# Schematic_Sensing_Module.net
KiCad netlist of a schematic drawn in EAGLE
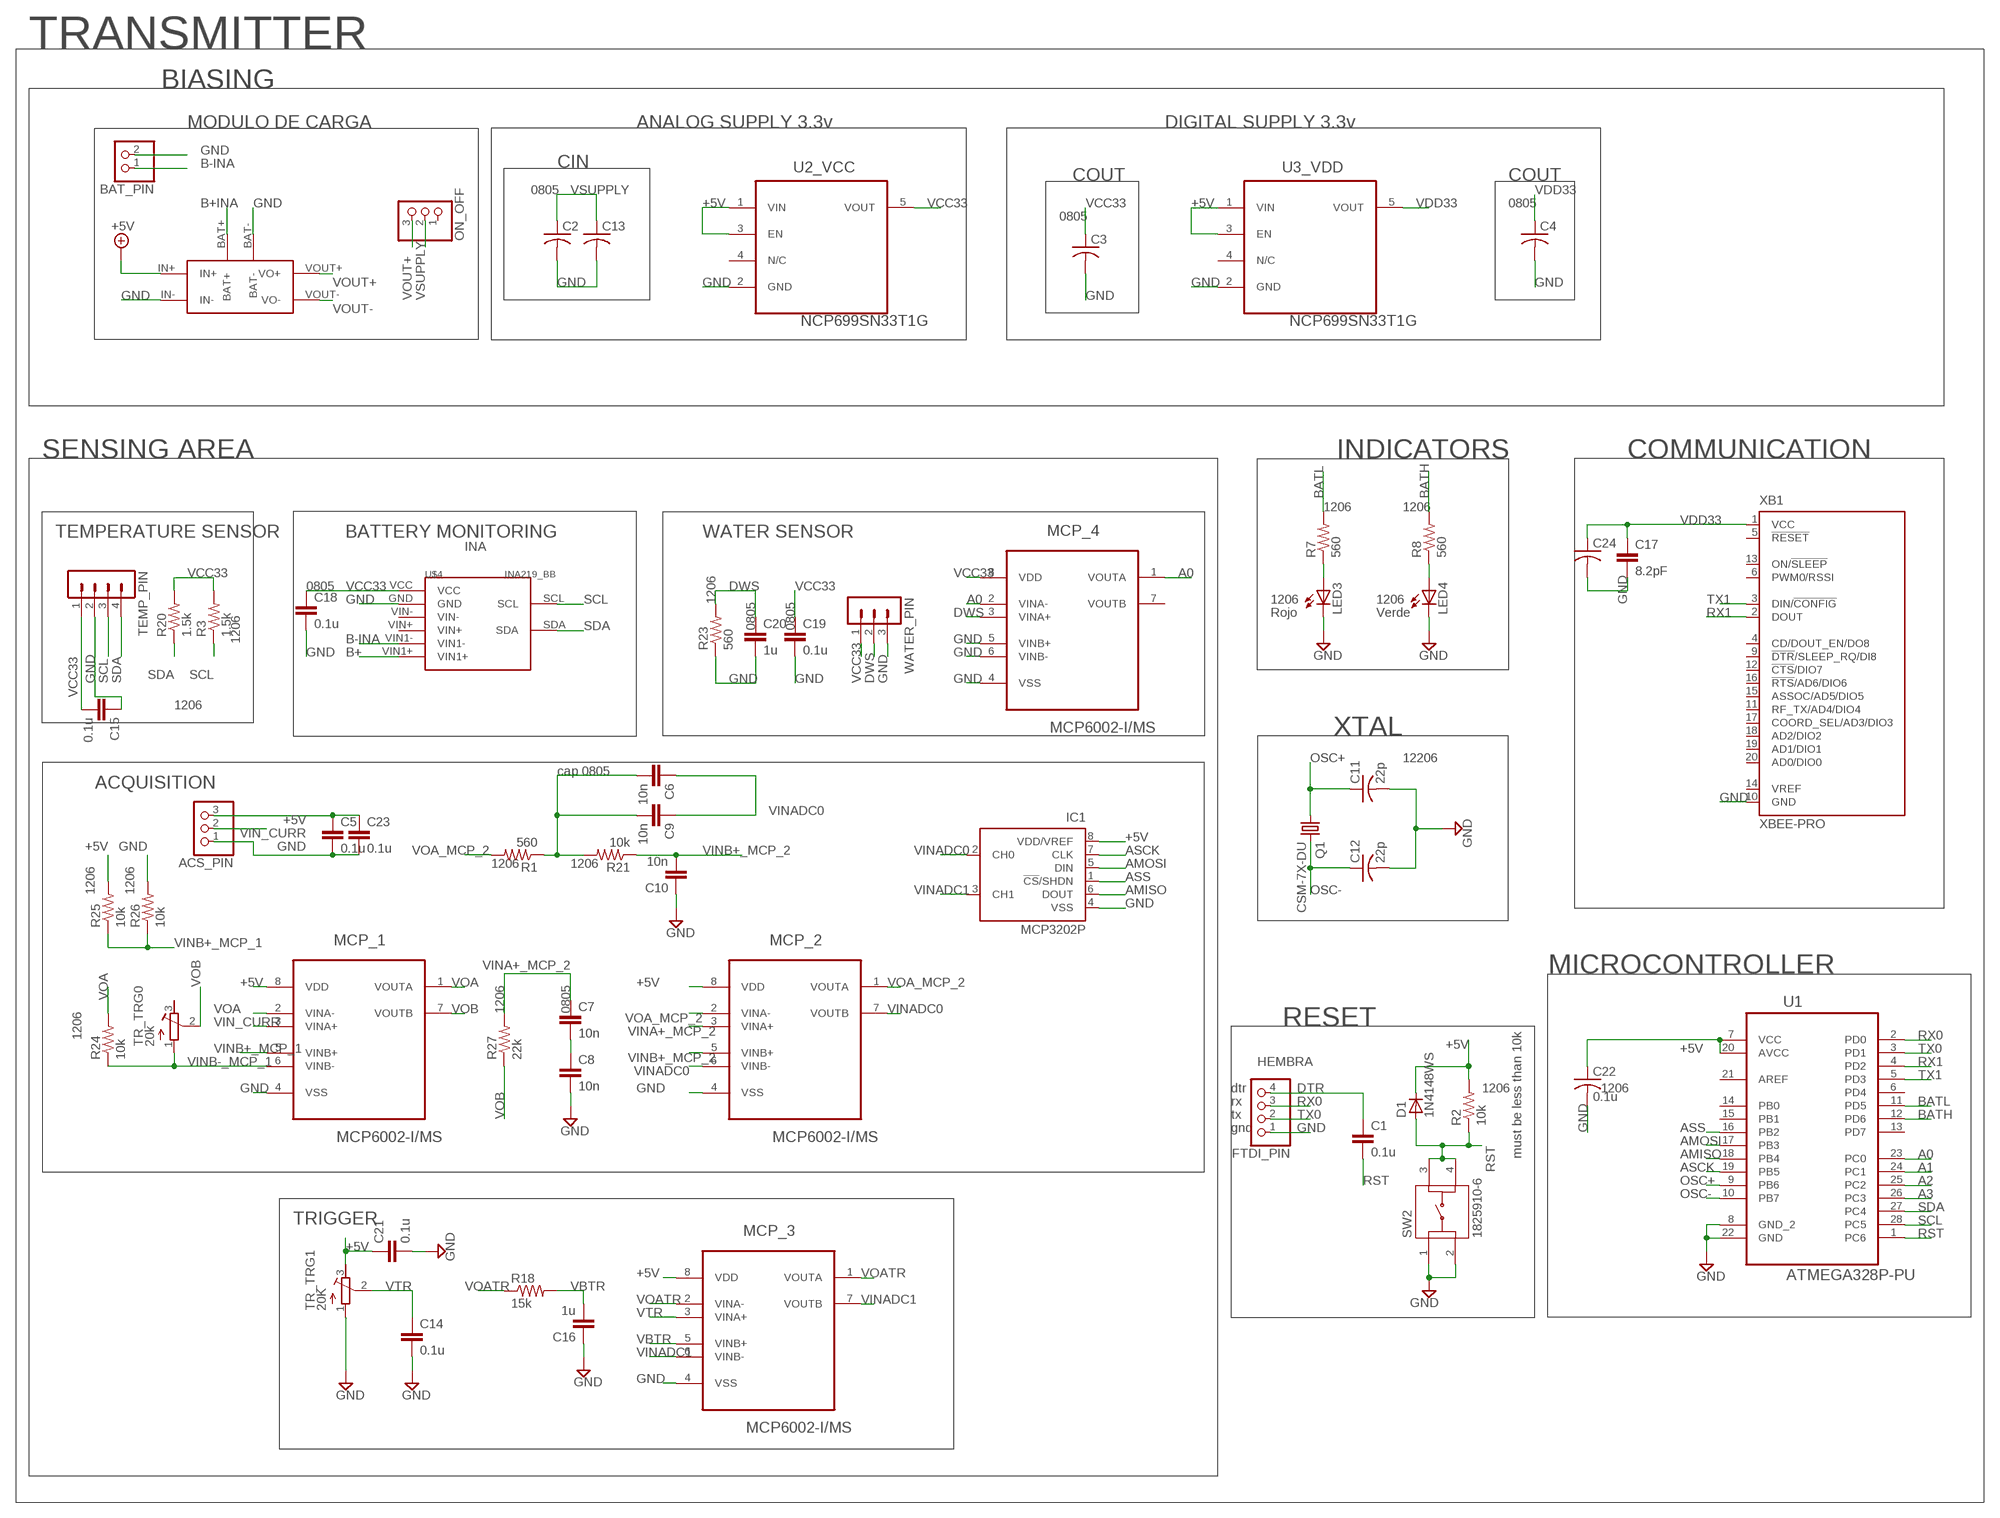
[diagram p0: schematic, sheet 1]

(export (version "E")
  (design (tool "Eeschema 10.0.6"))
  (components
    (comp (ref "ACS_PIN")
      (value "PINHD-1X3")
      (footprint "eagle-import:1X03")
      (libsource (lib "eagle-import") (part "PINHD-1X3"))
    )
    (comp (ref "BAT_PIN")
      (value "PINHD-1X2")
      (footprint "eagle-import:1X02")
      (libsource (lib "eagle-import") (part "PINHD-1X2"))
    )
    (comp (ref "C1")
      (value "0.1u")
      (footprint "eagle-import:C0805")
      (libsource (lib "eagle-import") (part "C-EUC0805"))
    )
    (comp (ref "C2")
      (value "C-USC0805")
      (footprint "eagle-import:C0805")
      (libsource (lib "eagle-import") (part "C-USC0805"))
    )
    (comp (ref "C3")
      (value "C-USC0805")
      (footprint "eagle-import:C0805")
      (libsource (lib "eagle-import") (part "C-USC0805"))
    )
    (comp (ref "C4")
      (value "C-USC0805")
      (footprint "eagle-import:C0805")
      (libsource (lib "eagle-import") (part "C-USC0805"))
    )
    (comp (ref "C5")
      (value "0.1u")
      (footprint "eagle-import:C0805")
      (libsource (lib "eagle-import") (part "C-EUC0805"))
    )
    (comp (ref "C6")
      (value "10n")
      (footprint "eagle-import:C0805")
      (libsource (lib "eagle-import") (part "C-EUC0805"))
    )
    (comp (ref "C7")
      (value "10n")
      (footprint "eagle-import:C0805")
      (libsource (lib "eagle-import") (part "C-EUC0805"))
    )
    (comp (ref "C8")
      (value "10n")
      (footprint "eagle-import:C0805")
      (libsource (lib "eagle-import") (part "C-EUC0805"))
    )
    (comp (ref "C9")
      (value "10n")
      (footprint "eagle-import:C0805")
      (libsource (lib "eagle-import") (part "C-EUC0805"))
    )
    (comp (ref "C10")
      (value "10n")
      (footprint "eagle-import:C0805")
      (libsource (lib "eagle-import") (part "C-EUC0805"))
    )
    (comp (ref "C11")
      (value "22p")
      (footprint "eagle-import:C1206")
      (libsource (lib "eagle-import") (part "C-USC1206"))
    )
    (comp (ref "C12")
      (value "22p")
      (footprint "eagle-import:C1206")
      (libsource (lib "eagle-import") (part "C-USC1206"))
    )
    (comp (ref "C13")
      (value "C-USC0805")
      (footprint "eagle-import:C0805")
      (libsource (lib "eagle-import") (part "C-USC0805"))
    )
    (comp (ref "C14")
      (value "0.1u")
      (footprint "eagle-import:C0805")
      (libsource (lib "eagle-import") (part "C-EUC0805"))
    )
    (comp (ref "C15")
      (value "0.1u")
      (footprint "eagle-import:C0805")
      (libsource (lib "eagle-import") (part "C-EUC0805"))
    )
    (comp (ref "C16")
      (value "1u")
      (footprint "eagle-import:C0805")
      (libsource (lib "eagle-import") (part "C-EUC0805"))
    )
    (comp (ref "C17")
      (value "8.2pF")
      (footprint "eagle-import:C0805")
      (libsource (lib "eagle-import") (part "C-EUC0805"))
    )
    (comp (ref "C18")
      (value "0.1u")
      (footprint "eagle-import:C0805")
      (libsource (lib "eagle-import") (part "C-EUC0805"))
    )
    (comp (ref "C19")
      (value "0.1u")
      (footprint "eagle-import:C0805")
      (libsource (lib "eagle-import") (part "C-EUC0805"))
    )
    (comp (ref "C20")
      (value "1u")
      (footprint "eagle-import:C0805")
      (libsource (lib "eagle-import") (part "C-EUC0805"))
    )
    (comp (ref "C21")
      (value "0.1u")
      (footprint "eagle-import:C0805")
      (libsource (lib "eagle-import") (part "C-EUC0805"))
    )
    (comp (ref "C22")
      (value "0.1u")
      (footprint "eagle-import:C1206")
      (libsource (lib "eagle-import") (part "C-USC1206"))
    )
    (comp (ref "C23")
      (value "0.1u")
      (footprint "eagle-import:C0805")
      (libsource (lib "eagle-import") (part "C-EUC0805"))
    )
    (comp (ref "C24")
      (value "C-USC0805")
      (footprint "eagle-import:C0805")
      (libsource (lib "eagle-import") (part "C-USC0805"))
    )
    (comp (ref "D1")
      (value "1N4148WS")
      (footprint "eagle-import:SOD323")
      (fields (field (name "MF") "ON Semiconductor"))
      (libsource (lib "eagle-import") (part "1N4148WS"))
    )
    (comp (ref "FTDI_PIN")
      (value "PINHD-1X4")
      (footprint "eagle-import:1X04")
      (libsource (lib "eagle-import") (part "PINHD-1X4"))
    )
    (comp (ref "IC1")
      (value "MCP3202P")
      (footprint "eagle-import:DIL8")
      (fields (field (name "MF") "MICROCHIP") (field (name "MPN") "MCP3202-CI/P"))
      (libsource (lib "eagle-import") (part "MCP3202P"))
    )
    (comp (ref "LED3")
      (value "LEDCHIPLED_1206")
      (footprint "eagle-import:CHIPLED_1206")
      (libsource (lib "eagle-import") (part "LEDCHIPLED_1206"))
    )
    (comp (ref "LED4")
      (value "LEDCHIPLED_1206")
      (footprint "eagle-import:CHIPLED_1206")
      (libsource (lib "eagle-import") (part "LEDCHIPLED_1206"))
    )
    (comp (ref "MCP_1")
      (value "MCP6002-I/MS")
      (footprint "eagle-import:SOP65P490X110-8N")
      (fields (field (name "MF") "Microchip"))
      (libsource (lib "eagle-import") (part "MCP6002-I_MS-2_MCP6002-I/MS"))
    )
    (comp (ref "MCP_2")
      (value "MCP6002-I/MS")
      (footprint "eagle-import:SOP65P490X110-8N")
      (fields (field (name "DIGI-KEY_PART_NUMBER") "MCP6002-I/MS-ND") (field (name "MF") "Microchip"))
      (libsource (lib "eagle-import") (part "MCP6002-I/MS"))
    )
    (comp (ref "MCP_3")
      (value "MCP6002-I/MS")
      (footprint "eagle-import:SOP65P490X110-8N")
      (fields (field (name "DIGI-KEY_PART_NUMBER") "MCP6002-I/MS-ND") (field (name "MF") "Microchip"))
      (libsource (lib "eagle-import") (part "MCP6002-I/MS"))
    )
    (comp (ref "MCP_4")
      (value "MCP6002-I/MS")
      (footprint "eagle-import:SOP65P490X110-8N")
      (fields (field (name "DIGI-KEY_PART_NUMBER") "MCP6002-I/MS-ND") (field (name "MF") "Microchip"))
      (libsource (lib "eagle-import") (part "MCP6002-I/MS"))
    )
    (comp (ref "ON_OFF")
      (value "PINHD-1X3")
      (footprint "eagle-import:1X03")
      (libsource (lib "eagle-import") (part "PINHD-1X3"))
    )
    (comp (ref "Q1")
      (value "CSM-7X-DU")
      (footprint "eagle-import:CSM-7X-DU")
      (libsource (lib "eagle-import") (part "CSM-7X-DU"))
    )
    (comp (ref "R1")
      (value "560")
      (footprint "eagle-import:R1206")
      (libsource (lib "eagle-import") (part "R-US_R1206"))
    )
    (comp (ref "R2")
      (value "10k")
      (footprint "eagle-import:R1206")
      (libsource (lib "eagle-import") (part "R-US_R1206"))
    )
    (comp (ref "R3")
      (value "1.5k")
      (footprint "eagle-import:R1206")
      (libsource (lib "eagle-import") (part "R-US_R1206"))
    )
    (comp (ref "R7")
      (value "560")
      (footprint "eagle-import:R1206")
      (libsource (lib "eagle-import") (part "R-US_R1206"))
    )
    (comp (ref "R8")
      (value "560")
      (footprint "eagle-import:R1206")
      (libsource (lib "eagle-import") (part "R-US_R1206"))
    )
    (comp (ref "R18")
      (value "15k")
      (footprint "eagle-import:R0805")
      (libsource (lib "eagle-import") (part "resistor_R-US_R0805"))
    )
    (comp (ref "R20")
      (value "1.5k")
      (footprint "eagle-import:R1206")
      (libsource (lib "eagle-import") (part "R-US_R1206"))
    )
    (comp (ref "R21")
      (value "10k")
      (footprint "eagle-import:R1206")
      (libsource (lib "eagle-import") (part "R-US_R1206"))
    )
    (comp (ref "R23")
      (value "560")
      (footprint "eagle-import:R1206")
      (libsource (lib "eagle-import") (part "R-US_R1206"))
    )
    (comp (ref "R24")
      (value "10k")
      (footprint "eagle-import:R1206")
      (libsource (lib "eagle-import") (part "R-US_R1206"))
    )
    (comp (ref "R25")
      (value "10k")
      (footprint "eagle-import:R1206")
      (libsource (lib "eagle-import") (part "R-US_R1206"))
    )
    (comp (ref "R26")
      (value "10k")
      (footprint "eagle-import:R1206")
      (libsource (lib "eagle-import") (part "R-US_R1206"))
    )
    (comp (ref "R27")
      (value "22k")
      (footprint "eagle-import:R1206")
      (libsource (lib "eagle-import") (part "R-US_R1206"))
    )
    (comp (ref "SW2")
      (value "1825910-6")
      (footprint "eagle-import:SW_1825910-6-4")
      (fields (field (name "MF") "TE Connectivity"))
      (libsource (lib "eagle-import") (part "1825910-6"))
    )
    (comp (ref "TEMP_PIN")
      (value "MA04-1")
      (footprint "eagle-import:MA04-1")
      (libsource (lib "eagle-import") (part "MA04-1"))
    )
    (comp (ref "TR_TRG0")
      (value "20k")
      (footprint "eagle-import:RTRIM64W")
      (libsource (lib "eagle-import") (part "R-TRIMM64W"))
    )
    (comp (ref "TR_TRG1")
      (value "20K")
      (footprint "eagle-import:RTRIM64W")
      (libsource (lib "eagle-import") (part "R-TRIMM64W"))
    )
    (comp (ref "U$1")
      (value "MODULO_CARGA_DEVICE")
      (footprint "eagle-import:MODULO_CARGA")
      (libsource (lib "eagle-import") (part "MODULO_CARGA_DEVICE"))
    )
    (comp (ref "U$4")
      (value "INA219_BB")
      (footprint "eagle-import:INA219_BB")
      (libsource (lib "eagle-import") (part "INA219_BB"))
    )
    (comp (ref "U1")
      (value "ATMEGA328P-PU")
      (footprint "eagle-import:DIP254P762X457-28")
      (libsource (lib "eagle-import") (part "ATMEGA328P-PU"))
    )
    (comp (ref "U2_VCC")
      (value "NCP699SN33T1G")
      (footprint "eagle-import:SOT95P275X110-5N")
      (fields
        (field (name "DIGI-KEY_PART_NUMBER") "NCP699SN33T1GOSCT-ND")
        (field (name "MF") "ON Semiconductor")
      )
      (libsource (lib "eagle-import") (part "NCP699SN33T1G"))
    )
    (comp (ref "U3_VDD")
      (value "NCP699SN33T1G")
      (footprint "eagle-import:SOT95P275X110-5N")
      (fields
        (field (name "DIGI-KEY_PART_NUMBER") "NCP699SN33T1GOSCT-ND")
        (field (name "MF") "ON Semiconductor")
      )
      (libsource (lib "eagle-import") (part "NCP699SN33T1G"))
    )
    (comp (ref "WATER_PIN")
      (value "MA03-1")
      (footprint "eagle-import:MA03-1")
      (libsource (lib "eagle-import") (part "MA03-1"))
    )
    (comp (ref "XB1")
      (value "XBEE-PRO")
      (footprint "eagle-import:XBEE-PRO")
      (fields (field (name "MPN") "XBP24-AWI-001"))
      (libsource (lib "eagle-import") (part "XBEE-PRO"))
    )
  )
  (nets
    (net (code "1") (name "+5V") (class "Default")
      (node (ref "ACS_PIN") (pin "3") (pinfunction "3_3") (pintype "passive"))
      (node (ref "C21") (pin "1") (pinfunction "1_1") (pintype "passive"))
      (node (ref "C22") (pin "1") (pinfunction "1_1") (pintype "passive"))
      (node (ref "C23") (pin "1") (pinfunction "1_1") (pintype "passive"))
      (node (ref "C5") (pin "1") (pinfunction "1_1") (pintype "passive"))
      (node (ref "D1") (pin "C") (pinfunction "C_C") (pintype "passive"))
      (node (ref "IC1") (pin "8") (pinfunction "VDD/VREF_8") (pintype "input"))
      (node (ref "MCP_1") (pin "8") (pinfunction "VDD_8") (pintype "power_in"))
      (node (ref "MCP_2") (pin "8") (pinfunction "VDD_8") (pintype "power_in"))
      (node (ref "MCP_3") (pin "8") (pinfunction "VDD_8") (pintype "power_in"))
      (node (ref "R2") (pin "2") (pinfunction "2_2") (pintype "passive"))
      (node (ref "R25") (pin "2") (pinfunction "2_2") (pintype "passive"))
      (node (ref "TR_TRG1") (pin "3") (pinfunction "E_3") (pintype "passive"))
      (node (ref "U$1") (pin "IN+") (pinfunction "IN+_IN+") (pintype "bidirectional"))
      (node (ref "U1") (pin "20") (pinfunction "AVCC_20") (pintype "power_in"))
      (node (ref "U1") (pin "7") (pinfunction "VCC_7") (pintype "power_in"))
      (node (ref "U2_VCC") (pin "1") (pinfunction "VIN_1") (pintype "power_in"))
      (node (ref "U2_VCC") (pin "3") (pinfunction "EN_3") (pintype "input"))
      (node (ref "U3_VDD") (pin "1") (pinfunction "VIN_1") (pintype "power_in"))
      (node (ref "U3_VDD") (pin "3") (pinfunction "EN_3") (pintype "input"))
    )
    (net (code "2") (name "/A0") (class "Default")
      (node (ref "MCP_4") (pin "1") (pinfunction "VOUTA_1") (pintype "output"))
      (node (ref "MCP_4") (pin "2") (pinfunction "VINA-_2") (pintype "input"))
      (node (ref "U1") (pin "23") (pinfunction "PC0_23") (pintype "bidirectional"))
    )
    (net (code "3") (name "/A1") (class "Default")
      (node (ref "U1") (pin "24") (pinfunction "PC1_24") (pintype "bidirectional"))
    )
    (net (code "4") (name "/A2") (class "Default")
      (node (ref "U1") (pin "25") (pinfunction "PC2_25") (pintype "bidirectional"))
    )
    (net (code "5") (name "/A3") (class "Default")
      (node (ref "U1") (pin "26") (pinfunction "PC3_26") (pintype "bidirectional"))
    )
    (net (code "6") (name "/AMISO") (class "Default")
      (node (ref "IC1") (pin "6") (pinfunction "DOUT_6") (pintype "input"))
      (node (ref "U1") (pin "18") (pinfunction "PB4_18") (pintype "bidirectional"))
    )
    (net (code "7") (name "/AMOSI") (class "Default")
      (node (ref "IC1") (pin "5") (pinfunction "DIN_5") (pintype "input"))
      (node (ref "U1") (pin "17") (pinfunction "PB3_17") (pintype "bidirectional"))
    )
    (net (code "8") (name "/ASCK") (class "Default")
      (node (ref "IC1") (pin "7") (pinfunction "CLK_7") (pintype "input"))
      (node (ref "U1") (pin "19") (pinfunction "PB5_19") (pintype "bidirectional"))
    )
    (net (code "9") (name "/ASS") (class "Default")
      (node (ref "IC1") (pin "1") (pinfunction "~{CS}/SHDN_1") (pintype "input"))
      (node (ref "U1") (pin "16") (pinfunction "PB2_16") (pintype "bidirectional"))
    )
    (net (code "10") (name "/B+") (class "Default")
      (node (ref "U$4") (pin "VIN1+") (pinfunction "VIN1+_VIN1+") (pintype "bidirectional"))
    )
    (net (code "11") (name "/B+INA") (class "Default")
      (node (ref "U$1") (pin "BAT+") (pinfunction "BAT+_BAT+") (pintype "bidirectional"))
    )
    (net (code "12") (name "/B-INA") (class "Default")
      (node (ref "BAT_PIN") (pin "1") (pinfunction "1_1") (pintype "passive"))
      (node (ref "U$4") (pin "VIN1-") (pinfunction "VIN1-_VIN1-") (pintype "bidirectional"))
    )
    (net (code "13") (name "/BATH") (class "Default")
      (node (ref "R8") (pin "2") (pinfunction "2_2") (pintype "passive"))
      (node (ref "U1") (pin "12") (pinfunction "PD6_12") (pintype "bidirectional"))
    )
    (net (code "14") (name "/BATL") (class "Default")
      (node (ref "R7") (pin "2") (pinfunction "2_2") (pintype "passive"))
      (node (ref "U1") (pin "11") (pinfunction "PD5_11") (pintype "bidirectional"))
    )
    (net (code "15") (name "/DTR") (class "Default")
      (node (ref "C1") (pin "1") (pinfunction "1_1") (pintype "passive"))
      (node (ref "FTDI_PIN") (pin "4") (pinfunction "4_4") (pintype "passive"))
    )
    (net (code "16") (name "/DWS") (class "Default")
      (node (ref "C20") (pin "1") (pinfunction "1_1") (pintype "passive"))
      (node (ref "MCP_4") (pin "3") (pinfunction "VINA+_3") (pintype "input"))
      (node (ref "R23") (pin "2") (pinfunction "2_2") (pintype "passive"))
      (node (ref "WATER_PIN") (pin "2") (pinfunction "2_2") (pintype "passive"))
    )
    (net (code "17") (name "/OSC+") (class "Default")
      (node (ref "C11") (pin "1") (pinfunction "1_1") (pintype "passive"))
      (node (ref "Q1") (pin "1") (pinfunction "1_1") (pintype "passive"))
      (node (ref "U1") (pin "9") (pinfunction "PB6_9") (pintype "bidirectional"))
    )
    (net (code "18") (name "/OSC-") (class "Default")
      (node (ref "C12") (pin "1") (pinfunction "1_1") (pintype "passive"))
      (node (ref "Q1") (pin "2") (pinfunction "2_2") (pintype "passive"))
      (node (ref "U1") (pin "10") (pinfunction "PB7_10") (pintype "bidirectional"))
    )
    (net (code "19") (name "/RST") (class "Default")
      (node (ref "C1") (pin "2") (pinfunction "2_2") (pintype "passive"))
      (node (ref "D1") (pin "A") (pinfunction "A_A") (pintype "passive"))
      (node (ref "R2") (pin "1") (pinfunction "1_1") (pintype "passive"))
      (node (ref "SW2") (pin "3") (pinfunction "3_3") (pintype "passive"))
      (node (ref "SW2") (pin "4") (pinfunction "4_4") (pintype "passive"))
      (node (ref "U1") (pin "1") (pinfunction "PC6_1") (pintype "bidirectional"))
    )
    (net (code "20") (name "/RX0") (class "Default")
      (node (ref "FTDI_PIN") (pin "3") (pinfunction "3_3") (pintype "passive"))
      (node (ref "U1") (pin "2") (pinfunction "PD0_2") (pintype "bidirectional"))
    )
    (net (code "21") (name "/RX1") (class "Default")
      (node (ref "U1") (pin "4") (pinfunction "PD2_4") (pintype "bidirectional"))
      (node (ref "XB1") (pin "2") (pinfunction "DOUT_2") (pintype "output"))
    )
    (net (code "22") (name "/SCL") (class "Default")
      (node (ref "R3") (pin "1") (pinfunction "1_1") (pintype "passive"))
      (node (ref "TEMP_PIN") (pin "3") (pinfunction "3_3") (pintype "passive"))
      (node (ref "U$4") (pin "SCL") (pinfunction "SCL_SCL") (pintype "bidirectional"))
      (node (ref "U1") (pin "28") (pinfunction "PC5_28") (pintype "bidirectional"))
    )
    (net (code "23") (name "/SDA") (class "Default")
      (node (ref "R20") (pin "1") (pinfunction "1_1") (pintype "passive"))
      (node (ref "TEMP_PIN") (pin "4") (pinfunction "4_4") (pintype "passive"))
      (node (ref "U$4") (pin "SDA") (pinfunction "SDA_SDA") (pintype "bidirectional"))
      (node (ref "U1") (pin "27") (pinfunction "PC4_27") (pintype "bidirectional"))
    )
    (net (code "24") (name "/TX0") (class "Default")
      (node (ref "FTDI_PIN") (pin "2") (pinfunction "2_2") (pintype "passive"))
      (node (ref "U1") (pin "3") (pinfunction "PD1_3") (pintype "bidirectional"))
    )
    (net (code "25") (name "/TX1") (class "Default")
      (node (ref "U1") (pin "5") (pinfunction "PD3_5") (pintype "bidirectional"))
      (node (ref "XB1") (pin "3") (pinfunction "DIN/~{CONFIG}_3") (pintype "input"))
    )
    (net (code "26") (name "/VBTR") (class "Default")
      (node (ref "C16") (pin "2") (pinfunction "2_2") (pintype "passive"))
      (node (ref "MCP_3") (pin "5") (pinfunction "VINB+_5") (pintype "input"))
      (node (ref "R18") (pin "2") (pinfunction "2_2") (pintype "passive"))
    )
    (net (code "27") (name "/VCC33") (class "Default")
      (node (ref "C15") (pin "2") (pinfunction "2_2") (pintype "passive"))
      (node (ref "C18") (pin "1") (pinfunction "1_1") (pintype "passive"))
      (node (ref "C19") (pin "1") (pinfunction "1_1") (pintype "passive"))
      (node (ref "C3") (pin "1") (pinfunction "1_1") (pintype "passive"))
      (node (ref "MCP_4") (pin "8") (pinfunction "VDD_8") (pintype "power_in"))
      (node (ref "R20") (pin "2") (pinfunction "2_2") (pintype "passive"))
      (node (ref "R3") (pin "2") (pinfunction "2_2") (pintype "passive"))
      (node (ref "TEMP_PIN") (pin "1") (pinfunction "1_1") (pintype "passive"))
      (node (ref "U$4") (pin "VCC") (pinfunction "VCC_VCC") (pintype "bidirectional"))
      (node (ref "U2_VCC") (pin "5") (pinfunction "VOUT_5") (pintype "output"))
      (node (ref "WATER_PIN") (pin "1") (pinfunction "1_1") (pintype "passive"))
    )
    (net (code "28") (name "/VDD33") (class "Default")
      (node (ref "C17") (pin "1") (pinfunction "1_1") (pintype "passive"))
      (node (ref "C24") (pin "1") (pinfunction "1_1") (pintype "passive"))
      (node (ref "C4") (pin "1") (pinfunction "1_1") (pintype "passive"))
      (node (ref "U3_VDD") (pin "5") (pinfunction "VOUT_5") (pintype "output"))
      (node (ref "XB1") (pin "1") (pinfunction "VCC_1") (pintype "power_in"))
    )
    (net (code "29") (name "/VINA+_MCP_2") (class "Default")
      (node (ref "C7") (pin "1") (pinfunction "1_1") (pintype "passive"))
      (node (ref "MCP_2") (pin "3") (pinfunction "VINA+_3") (pintype "input"))
      (node (ref "R27") (pin "2") (pinfunction "2_2") (pintype "passive"))
    )
    (net (code "30") (name "/VINADC0") (class "Default")
      (node (ref "C6") (pin "1") (pinfunction "1_1") (pintype "passive"))
      (node (ref "C9") (pin "1") (pinfunction "1_1") (pintype "passive"))
      (node (ref "IC1") (pin "2") (pinfunction "CH0_2") (pintype "input"))
      (node (ref "MCP_2") (pin "6") (pinfunction "VINB-_6") (pintype "input"))
      (node (ref "MCP_2") (pin "7") (pinfunction "VOUTB_7") (pintype "output"))
    )
    (net (code "31") (name "/VINADC1") (class "Default")
      (node (ref "IC1") (pin "3") (pinfunction "CH1_3") (pintype "input"))
      (node (ref "MCP_3") (pin "6") (pinfunction "VINB-_6") (pintype "input"))
      (node (ref "MCP_3") (pin "7") (pinfunction "VOUTB_7") (pintype "output"))
    )
    (net (code "32") (name "/VINB+_MCP_1") (class "Default")
      (node (ref "MCP_1") (pin "5") (pinfunction "VINB+_5") (pintype "input"))
      (node (ref "R25") (pin "1") (pinfunction "1_1") (pintype "passive"))
      (node (ref "R26") (pin "1") (pinfunction "1_1") (pintype "passive"))
    )
    (net (code "33") (name "/VINB+_MCP_2") (class "Default")
      (node (ref "C10") (pin "2") (pinfunction "2_2") (pintype "passive"))
      (node (ref "MCP_2") (pin "5") (pinfunction "VINB+_5") (pintype "input"))
      (node (ref "R21") (pin "1") (pinfunction "1_1") (pintype "passive"))
    )
    (net (code "34") (name "/VINB-_MCP_1") (class "Default")
      (node (ref "MCP_1") (pin "6") (pinfunction "VINB-_6") (pintype "input"))
      (node (ref "R24") (pin "1") (pinfunction "1_1") (pintype "passive"))
      (node (ref "TR_TRG0") (pin "1") (pinfunction "A_1") (pintype "passive"))
    )
    (net (code "35") (name "/VIN_CURR") (class "Default")
      (node (ref "ACS_PIN") (pin "2") (pinfunction "2_2") (pintype "passive"))
      (node (ref "MCP_1") (pin "3") (pinfunction "VINA+_3") (pintype "input"))
    )
    (net (code "36") (name "/VOA") (class "Default")
      (node (ref "MCP_1") (pin "1") (pinfunction "VOUTA_1") (pintype "output"))
      (node (ref "MCP_1") (pin "2") (pinfunction "VINA-_2") (pintype "input"))
      (node (ref "R24") (pin "2") (pinfunction "2_2") (pintype "passive"))
    )
    (net (code "37") (name "/VOATR") (class "Default")
      (node (ref "MCP_3") (pin "1") (pinfunction "VOUTA_1") (pintype "output"))
      (node (ref "MCP_3") (pin "2") (pinfunction "VINA-_2") (pintype "input"))
      (node (ref "R18") (pin "1") (pinfunction "1_1") (pintype "passive"))
    )
    (net (code "38") (name "/VOA_MCP_2") (class "Default")
      (node (ref "MCP_2") (pin "1") (pinfunction "VOUTA_1") (pintype "output"))
      (node (ref "MCP_2") (pin "2") (pinfunction "VINA-_2") (pintype "input"))
      (node (ref "R1") (pin "2") (pinfunction "2_2") (pintype "passive"))
    )
    (net (code "39") (name "/VOB") (class "Default")
      (node (ref "MCP_1") (pin "7") (pinfunction "VOUTB_7") (pintype "output"))
      (node (ref "R27") (pin "1") (pinfunction "1_1") (pintype "passive"))
      (node (ref "TR_TRG0") (pin "2") (pinfunction "S_2") (pintype "passive"))
    )
    (net (code "40") (name "/VOUT+") (class "Default")
      (node (ref "ON_OFF") (pin "3") (pinfunction "3_3") (pintype "passive"))
      (node (ref "U$1") (pin "VOUT+") (pinfunction "VO+_VOUT+") (pintype "bidirectional"))
    )
    (net (code "41") (name "/VOUT-") (class "Default")
      (node (ref "U$1") (pin "VOUT-") (pinfunction "VO-_VOUT-") (pintype "bidirectional"))
    )
    (net (code "42") (name "/VSUPPLY") (class "Default")
      (node (ref "C13") (pin "1") (pinfunction "1_1") (pintype "passive"))
      (node (ref "C2") (pin "1") (pinfunction "1_1") (pintype "passive"))
      (node (ref "ON_OFF") (pin "2") (pinfunction "2_2") (pintype "passive"))
    )
    (net (code "43") (name "/VTR") (class "Default")
      (node (ref "C14") (pin "1") (pinfunction "1_1") (pintype "passive"))
      (node (ref "MCP_3") (pin "3") (pinfunction "VINA+_3") (pintype "input"))
      (node (ref "TR_TRG1") (pin "2") (pinfunction "S_2") (pintype "passive"))
    )
    (net (code "44") (name "GND") (class "Default")
      (node (ref "ACS_PIN") (pin "1") (pinfunction "1_1") (pintype "passive"))
      (node (ref "BAT_PIN") (pin "2") (pinfunction "2_2") (pintype "passive"))
      (node (ref "C10") (pin "1") (pinfunction "1_1") (pintype "passive"))
      (node (ref "C11") (pin "2") (pinfunction "2_2") (pintype "passive"))
      (node (ref "C12") (pin "2") (pinfunction "2_2") (pintype "passive"))
      (node (ref "C13") (pin "2") (pinfunction "2_2") (pintype "passive"))
      (node (ref "C14") (pin "2") (pinfunction "2_2") (pintype "passive"))
      (node (ref "C15") (pin "1") (pinfunction "1_1") (pintype "passive"))
      (node (ref "C16") (pin "1") (pinfunction "1_1") (pintype "passive"))
      (node (ref "C17") (pin "2") (pinfunction "2_2") (pintype "passive"))
      (node (ref "C18") (pin "2") (pinfunction "2_2") (pintype "passive"))
      (node (ref "C19") (pin "2") (pinfunction "2_2") (pintype "passive"))
      (node (ref "C2") (pin "2") (pinfunction "2_2") (pintype "passive"))
      (node (ref "C20") (pin "2") (pinfunction "2_2") (pintype "passive"))
      (node (ref "C21") (pin "2") (pinfunction "2_2") (pintype "passive"))
      (node (ref "C22") (pin "2") (pinfunction "2_2") (pintype "passive"))
      (node (ref "C23") (pin "2") (pinfunction "2_2") (pintype "passive"))
      (node (ref "C24") (pin "2") (pinfunction "2_2") (pintype "passive"))
      (node (ref "C3") (pin "2") (pinfunction "2_2") (pintype "passive"))
      (node (ref "C4") (pin "2") (pinfunction "2_2") (pintype "passive"))
      (node (ref "C5") (pin "2") (pinfunction "2_2") (pintype "passive"))
      (node (ref "C8") (pin "2") (pinfunction "2_2") (pintype "passive"))
      (node (ref "FTDI_PIN") (pin "1") (pinfunction "1_1") (pintype "passive"))
      (node (ref "IC1") (pin "4") (pinfunction "VSS_4") (pintype "input"))
      (node (ref "LED3") (pin "C") (pinfunction "C_C") (pintype "passive"))
      (node (ref "LED4") (pin "C") (pinfunction "C_C") (pintype "passive"))
      (node (ref "MCP_1") (pin "4") (pinfunction "VSS_4") (pintype "power_in"))
      (node (ref "MCP_2") (pin "4") (pinfunction "VSS_4") (pintype "power_in"))
      (node (ref "MCP_3") (pin "4") (pinfunction "VSS_4") (pintype "power_in"))
      (node (ref "MCP_4") (pin "4") (pinfunction "VSS_4") (pintype "power_in"))
      (node (ref "MCP_4") (pin "5") (pinfunction "VINB+_5") (pintype "input"))
      (node (ref "MCP_4") (pin "6") (pinfunction "VINB-_6") (pintype "input"))
      (node (ref "R23") (pin "1") (pinfunction "1_1") (pintype "passive"))
      (node (ref "R26") (pin "2") (pinfunction "2_2") (pintype "passive"))
      (node (ref "SW2") (pin "1") (pinfunction "1_1") (pintype "passive"))
      (node (ref "SW2") (pin "2") (pinfunction "2_2") (pintype "passive"))
      (node (ref "TEMP_PIN") (pin "2") (pinfunction "2_2") (pintype "passive"))
      (node (ref "TR_TRG1") (pin "1") (pinfunction "A_1") (pintype "passive"))
      (node (ref "U$1") (pin "BAT-") (pinfunction "BAT-_BAT-") (pintype "bidirectional"))
      (node (ref "U$1") (pin "IN-") (pinfunction "IN-_IN-") (pintype "bidirectional"))
      (node (ref "U$4") (pin "GND") (pinfunction "GND_GND") (pintype "bidirectional"))
      (node (ref "U1") (pin "22") (pinfunction "GND_22") (pintype "passive"))
      (node (ref "U1") (pin "8") (pinfunction "GND_2_8") (pintype "passive"))
      (node (ref "U2_VCC") (pin "2") (pinfunction "GND_2") (pintype "passive"))
      (node (ref "U3_VDD") (pin "2") (pinfunction "GND_2") (pintype "passive"))
      (node (ref "WATER_PIN") (pin "3") (pinfunction "3_3") (pintype "passive"))
      (node (ref "XB1") (pin "10") (pinfunction "GND_10") (pintype "power_in"))
    )
    (net (code "45") (name "Net-(C6-Pad2)") (class "Default")
      (node (ref "C6") (pin "2") (pinfunction "2_2") (pintype "passive"))
      (node (ref "C9") (pin "2") (pinfunction "2_2") (pintype "passive"))
      (node (ref "R1") (pin "1") (pinfunction "1_1") (pintype "passive"))
      (node (ref "R21") (pin "2") (pinfunction "2_2") (pintype "passive"))
    )
    (net (code "46") (name "Net-(C7-Pad2)") (class "Default")
      (node (ref "C7") (pin "2") (pinfunction "2_2") (pintype "passive"))
      (node (ref "C8") (pin "1") (pinfunction "1_1") (pintype "passive"))
    )
    (net (code "47") (name "Net-(LED3-PadA)") (class "Default")
      (node (ref "LED3") (pin "A") (pinfunction "A_A") (pintype "passive"))
      (node (ref "R7") (pin "1") (pinfunction "1_1") (pintype "passive"))
    )
    (net (code "48") (name "Net-(LED4-PadA)") (class "Default")
      (node (ref "LED4") (pin "A") (pinfunction "A_A") (pintype "passive"))
      (node (ref "R8") (pin "1") (pinfunction "1_1") (pintype "passive"))
    )
    (net (code "49") (name "unconnected-(MCP_4-VOUTB-Pad7)") (class "Default")
      (node (ref "MCP_4") (pin "7") (pinfunction "VOUTB_7") (pintype "output"))
    )
    (net (code "50") (name "unconnected-(ON_OFF-Pad1)") (class "Default")
      (node (ref "ON_OFF") (pin "1") (pinfunction "1_1") (pintype "passive"))
    )
    (net (code "51") (name "unconnected-(TR_TRG0-E-Pad3)") (class "Default")
      (node (ref "TR_TRG0") (pin "3") (pinfunction "E_3") (pintype "passive"))
    )
    (net (code "52") (name "unconnected-(U$4-PadVIN+)") (class "Default")
      (node (ref "U$4") (pin "VIN+") (pinfunction "VIN+_VIN+") (pintype "bidirectional"))
    )
    (net (code "53") (name "unconnected-(U$4-PadVIN-)") (class "Default")
      (node (ref "U$4") (pin "VIN-") (pinfunction "VIN-_VIN-") (pintype "bidirectional"))
    )
    (net (code "54") (name "unconnected-(U1-AREF-Pad21)") (class "Default")
      (node (ref "U1") (pin "21") (pinfunction "AREF_21") (pintype "input"))
    )
    (net (code "55") (name "unconnected-(U1-PB0-Pad14)") (class "Default")
      (node (ref "U1") (pin "14") (pinfunction "PB0_14") (pintype "bidirectional"))
    )
    (net (code "56") (name "unconnected-(U1-PB1-Pad15)") (class "Default")
      (node (ref "U1") (pin "15") (pinfunction "PB1_15") (pintype "bidirectional"))
    )
    (net (code "57") (name "unconnected-(U1-PD4-Pad6)") (class "Default")
      (node (ref "U1") (pin "6") (pinfunction "PD4_6") (pintype "bidirectional"))
    )
    (net (code "58") (name "unconnected-(U1-PD7-Pad13)") (class "Default")
      (node (ref "U1") (pin "13") (pinfunction "PD7_13") (pintype "bidirectional"))
    )
    (net (code "59") (name "unconnected-(U2_VCC-N{slash}C-Pad4)") (class "Default")
      (node (ref "U2_VCC") (pin "4") (pinfunction "N/C_4") (pintype "no_connect"))
    )
    (net (code "60") (name "unconnected-(U3_VDD-N{slash}C-Pad4)") (class "Default")
      (node (ref "U3_VDD") (pin "4") (pinfunction "N/C_4") (pintype "no_connect"))
    )
    (net (code "61") (name "unconnected-(XB1-AD0{slash}DIO0-Pad20)") (class "Default")
      (node (ref "XB1") (pin "20") (pinfunction "AD0/DIO0_20") (pintype "bidirectional"))
    )
    (net (code "62") (name "unconnected-(XB1-AD1{slash}DIO1-Pad19)") (class "Default")
      (node (ref "XB1") (pin "19") (pinfunction "AD1/DIO1_19") (pintype "bidirectional"))
    )
    (net (code "63") (name "unconnected-(XB1-AD2{slash}DIO2-Pad18)") (class "Default")
      (node (ref "XB1") (pin "18") (pinfunction "AD2/DIO2_18") (pintype "bidirectional"))
    )
    (net (code "64") (name "unconnected-(XB1-ASSOC{slash}AD5{slash}DIO5-Pad15)") (class "Default")
      (node (ref "XB1") (pin "15") (pinfunction "ASSOC/AD5/DIO5_15") (pintype "bidirectional"))
    )
    (net (code "65") (name "unconnected-(XB1-CD{slash}DOUT_EN{slash}DO8-Pad4)") (class "Default")
      (node (ref "XB1") (pin "4") (pinfunction "CD/DOUT_EN/DO8_4") (pintype "output"))
    )
    (net (code "66") (name "unconnected-(XB1-COORD_SEL{slash}AD3{slash}DIO3-Pad17)") (class "Default")
      (node (ref "XB1") (pin "17") (pinfunction "COORD_SEL/AD3/DIO3_17") (pintype "bidirectional"))
    )
    (net (code "67") (name "unconnected-(XB1-ON{slash}~{SLEEP}-Pad13)") (class "Default")
      (node (ref "XB1") (pin "13") (pinfunction "ON/~{SLEEP}_13") (pintype "output"))
    )
    (net (code "68") (name "unconnected-(XB1-PWM0{slash}RSSI-Pad6)") (class "Default")
      (node (ref "XB1") (pin "6") (pinfunction "PWM0/RSSI_6") (pintype "output"))
    )
    (net (code "69") (name "unconnected-(XB1-RF_TX{slash}AD4{slash}DIO4-Pad11)") (class "Default")
      (node (ref "XB1") (pin "11") (pinfunction "RF_TX/AD4/DIO4_11") (pintype "bidirectional"))
    )
    (net (code "70") (name "unconnected-(XB1-VREF-Pad14)") (class "Default")
      (node (ref "XB1") (pin "14") (pinfunction "VREF_14") (pintype "input"))
    )
    (net (code "71") (name "unconnected-(XB1-~{CTS}{slash}DIO7-Pad12)") (class "Default")
      (node (ref "XB1") (pin "12") (pinfunction "~{CTS}/DIO7_12") (pintype "bidirectional"))
    )
    (net (code "72") (name "unconnected-(XB1-~{DTR}{slash}SLEEP_RQ{slash}DI8-Pad9)") (class "Default")
      (node (ref "XB1") (pin "9") (pinfunction "~{DTR}/SLEEP_RQ/DI8_9") (pintype "bidirectional"))
    )
    (net (code "73") (name "unconnected-(XB1-~{RESET}-Pad5)") (class "Default")
      (node (ref "XB1") (pin "5") (pinfunction "~{RESET}_5") (pintype "input"))
    )
    (net (code "74") (name "unconnected-(XB1-~{RTS}{slash}AD6{slash}DIO6-Pad16)") (class "Default")
      (node (ref "XB1") (pin "16") (pinfunction "~{RTS}/AD6/DIO6_16") (pintype "bidirectional"))
    )
  )
)
